# Uno_2022-03-31.net
KiCad netlist of a schematic drawn in Altium Designer
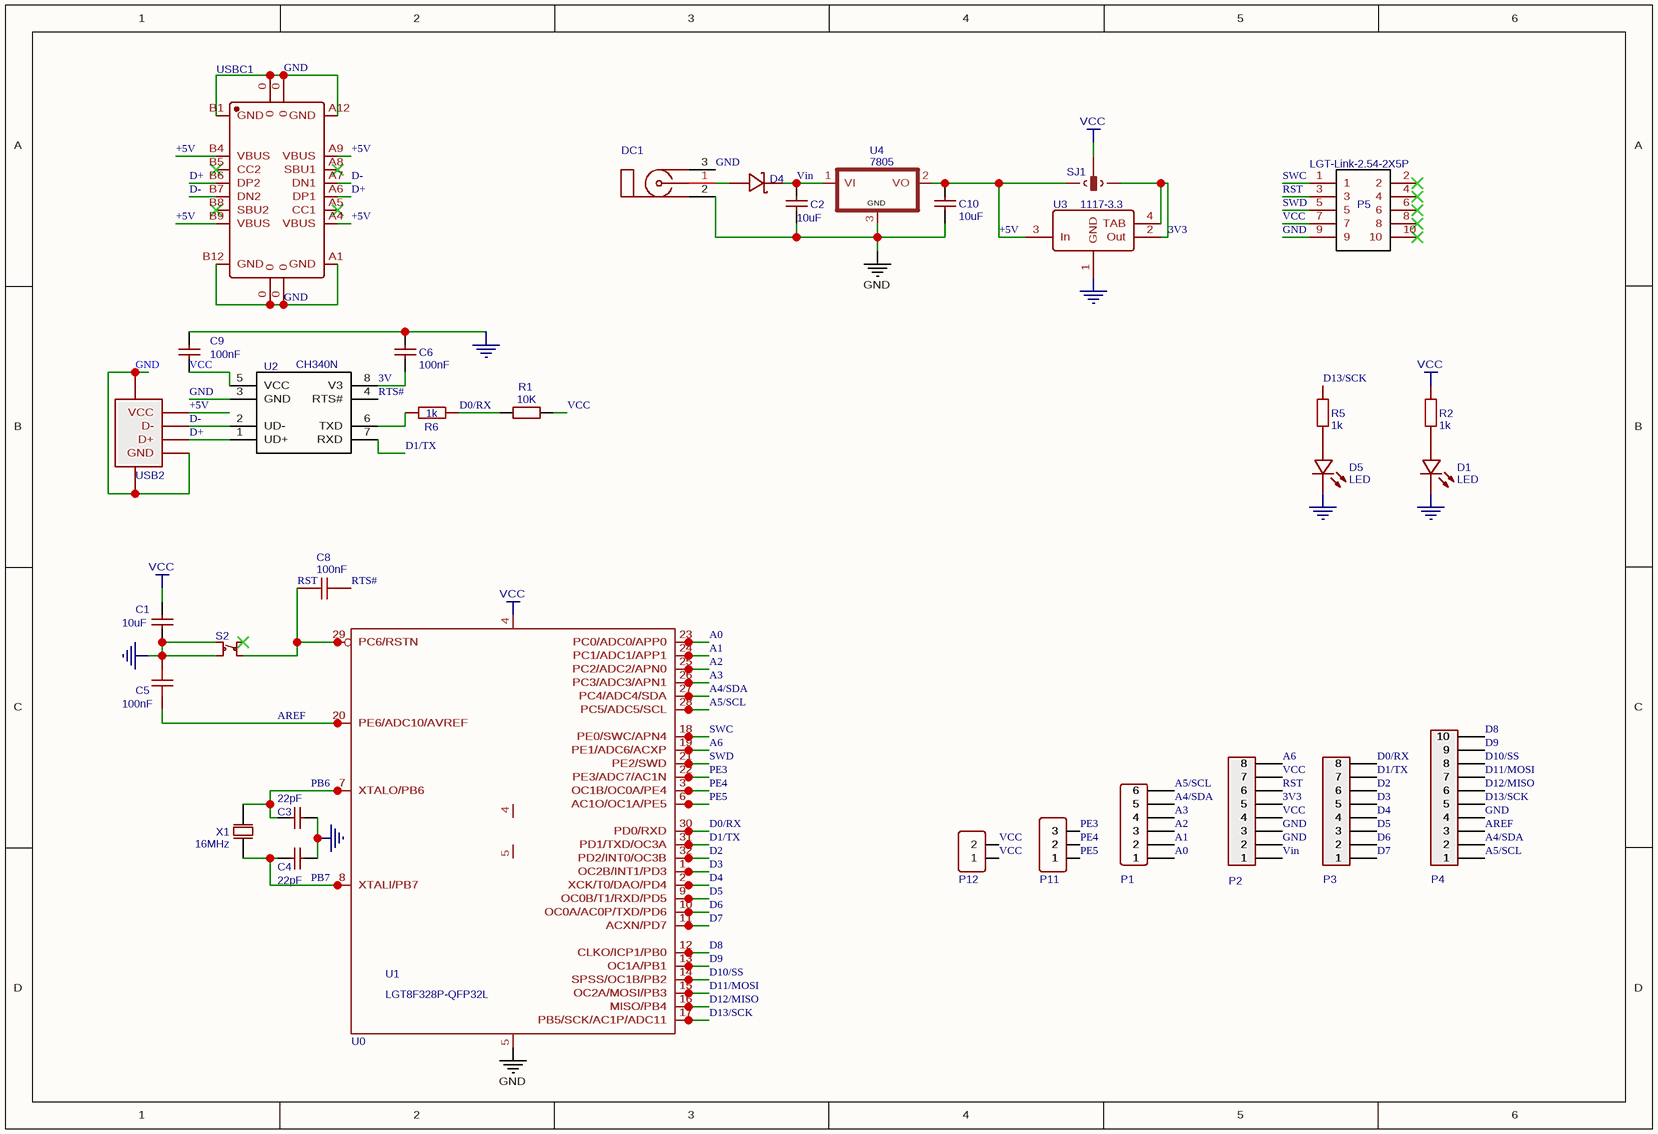
[diagram p0: Uno_2022-03-31.schdoc]

(export (version "E")
  (design (tool "Eeschema 10.0.6"))
  (components
    (comp (ref "C1")
      (value "10uF")
      (fields
        (field (name "VOLTAGE") "25V")
        (field (name "TOLERANCE") "±10%")
        (field (name "BOM_MANUFACTURER PART") "CL21A106KAYNNNE")
      )
      (libsource (lib "altium-import") (part "root_1_10uF_"))
    )
    (comp (ref "C2")
      (value "10uF")
      (fields
        (field (name "VOLTAGE") "25V")
        (field (name "TOLERANCE") "±10%")
        (field (name "BOM_MANUFACTURER PART") "CL21A106KAYNNNE")
      )
      (libsource (lib "altium-import") (part "root_1_10uF_"))
    )
    (comp (ref "C3")
      (value "22pF")
      (fields
        (field (name "VOLTAGE") "50V")
        (field (name "TOLERANCE") "±5%")
        (field (name "BOM_MANUFACTURER PART") "CL10C220JB8NNNC")
      )
      (libsource (lib "altium-import") (part "root_0_22pF_"))
    )
    (comp (ref "C4")
      (value "22pF")
      (fields
        (field (name "VOLTAGE") "50V")
        (field (name "TOLERANCE") "±5%")
        (field (name "BOM_MANUFACTURER PART") "CL10C220JB8NNNC")
      )
      (libsource (lib "altium-import") (part "root_0_22pF_"))
    )
    (comp (ref "C5")
      (value "100nF")
      (fields
        (field (name "VOLTAGE") "50V")
        (field (name "TOLERANCE") "±10%")
        (field (name "BOM_MANUFACTURER PART") "CC0603KRX7R9BB104")
      )
      (libsource (lib "") (part "root_1_100nF__1"))
    )
    (comp (ref "C6")
      (value "100nF")
      (fields
        (field (name "VOLTAGE") "25V")
        (field (name "TOLERANCE") "±10%")
        (field (name "BOM_MANUFACTURER PART") "CL21A106KAYNNNE")
      )
      (libsource (lib "altium-import") (part "root_1_100nF_"))
    )
    (comp (ref "C8")
      (value "100nF")
      (fields
        (field (name "VOLTAGE") "50V")
        (field (name "TOLERANCE") "±10%")
        (field (name "BOM_MANUFACTURER PART") "CC0603KRX7R9BB104")
      )
      (libsource (lib "altium-import") (part "root_2_100nF_"))
    )
    (comp (ref "C9")
      (value "100nF")
      (fields
        (field (name "VOLTAGE") "25V")
        (field (name "TOLERANCE") "±10%")
        (field (name "BOM_MANUFACTURER PART") "CL21A106KAYNNNE")
      )
      (libsource (lib "altium-import") (part "root_1_100nF_"))
    )
    (comp (ref "C10")
      (value "10uF")
      (fields
        (field (name "VOLTAGE") "25V")
        (field (name "TOLERANCE") "±10%")
        (field (name "BOM_MANUFACTURER PART") "CL21A106KAYNNNE")
      )
      (libsource (lib "altium-import") (part "root_1_10uF_"))
    )
    (comp (ref "D1")
      (value "LED")
      (fields (field (name "BOM_MANUFACTURER PART") "?"))
      (libsource (lib "altium-import") (part "root_3_LED_"))
    )
    (comp (ref "D4")
      (value "SS34")
      (fields (field (name "BOM_SUPPLIER PART") "C8678"))
      (libsource (lib "altium-import") (part "root_0_SS34_"))
    )
    (comp (ref "D5")
      (value "LED")
      (fields (field (name "BOM_MANUFACTURER PART") "?"))
      (libsource (lib "altium-import") (part "root_3_LED_"))
    )
    (comp (ref "DC1")
      (value "DC005-2.5MM")
      (fields (field (name "BOM_SUPPLIER PART") "C111573"))
      (libsource (lib "altium-import") (part "root_0_DC005-2.5MM_"))
    )
    (comp (ref "P1")
      (value "Header-Male-2.54_1x6")
      (fields (field (name "BOM_SUPPLIER PART") "C37208"))
      (libsource (lib "altium-import") (part "root_2_Header-Male-2.54_1x6_"))
    )
    (comp (ref "P2")
      (value "Header-Male-2.54_1x8")
      (fields (field (name "BOM_SUPPLIER PART") "E49256"))
      (libsource (lib "altium-import") (part "root_2_Header-Male-2.54_1x8_"))
    )
    (comp (ref "P3")
      (value "Header-Male-2.54_1x8")
      (fields (field (name "BOM_SUPPLIER PART") "E49256"))
      (libsource (lib "altium-import") (part "root_2_Header-Male-2.54_1x8_"))
    )
    (comp (ref "P4")
      (value "Header-Male-2.54_1x10")
      (fields
        (field (name "BOM_MANUFACTURER PART") "Header-Female-1.27_1x10")
        (field (name "BOM_SUPPLIER PART") "C29357")
      )
      (libsource (lib "altium-import") (part "root_2_Header-Male-2.54_1x10_"))
    )
    (comp (ref "P5")
      (value "LGT-Link-2.54-2X5P")
      (fields
        (field (name "BOM_MANUFACTURER PART") "IDC Box 2.54mm 2X5P")
        (field (name "BOM_SUPPLIER PART") "C5665")
      )
      (libsource (lib "altium-import") (part "root_0_LGT-Link-2.54-2X5P_"))
    )
    (comp (ref "P6")
      (value "Header-Female-2.54_1x3")
      (fields (field (name "BOM_SUPPLIER PART") "C146243"))
      (libsource (lib "altium-import") (part "root_2_Header-Female-2.54_1x3_"))
    )
    (comp (ref "P7")
      (value "Header-Male-2.54_1x8")
      (fields (field (name "BOM_SUPPLIER PART") "E49256"))
      (libsource (lib "altium-import") (part "root_2_Header-Male-2.54_1x8_"))
    )
    (comp (ref "P8")
      (value "Header-Male-2.54_1x10")
      (fields
        (field (name "BOM_MANUFACTURER PART") "Header-Female-1.27_1x10")
        (field (name "BOM_SUPPLIER PART") "C29357")
      )
      (libsource (lib "altium-import") (part "root_2_Header-Male-2.54_1x10_"))
    )
    (comp (ref "P9")
      (value "Header-Male-2.54_1x6")
      (fields (field (name "BOM_SUPPLIER PART") "C37208"))
      (libsource (lib "altium-import") (part "root_2_Header-Male-2.54_1x6_"))
    )
    (comp (ref "P10")
      (value "Header-Male-2.54_1x8")
      (fields (field (name "BOM_SUPPLIER PART") "E49256"))
      (libsource (lib "altium-import") (part "root_2_Header-Male-2.54_1x8_"))
    )
    (comp (ref "P11")
      (value "Header-Female-2.54_1x3")
      (fields (field (name "BOM_SUPPLIER PART") "C146243"))
      (libsource (lib "altium-import") (part "root_2_Header-Female-2.54_1x3_"))
    )
    (comp (ref "P12")
      (value "Header-Female-2.54_1x2")
      (fields
        (field (name "BOM_MANUFACTURER PART") "2.54-1*2PFemale")
        (field (name "BOM_SUPPLIER PART") "C49661")
      )
      (libsource (lib "altium-import") (part "root_2_Header-Female-2.54_1x2_"))
    )
    (comp (ref "R1")
      (value "10K")
      (fields
        (field (name "BOM_MANUFACTURER PART") "RS-03K103JT")
        (field (name "BOM_SUPPLIER PART") "C73809")
      )
      (libsource (lib "altium-import") (part "root_0_10K_"))
    )
    (comp (ref "R2")
      (value "1k")
      (fields (field (name "BOM_MANUFACTURER PART") "?"))
      (libsource (lib "altium-import") (part "root_1_1k_"))
    )
    (comp (ref "R5")
      (value "1k")
      (fields (field (name "BOM_MANUFACTURER PART") "?"))
      (libsource (lib "altium-import") (part "root_1_1k_"))
    )
    (comp (ref "R6")
      (value "1k")
      (fields (field (name "BOM_MANUFACTURER PART") "?"))
      (libsource (lib "altium-import") (part "root_0_1k_"))
    )
    (comp (ref "S2")
      (value "TS665CJ-A")
      (fields
        (field (name "BOM_SUPPLIER PART") "C393938")
        (field (name "BOM_MANUFACTURER PART") "TS665CJ")
        (field (name "CONTRIBUTOR") "回收站")
      )
      (libsource (lib "altium-import") (part "root_0_TS665CJ-A_"))
    )
    (comp (ref "SJ1")
      (value "JUMPER-PAD-3-2OF3_NC_BY_PASTE")
      (fields (field (name "BOM_MANUFACTURER PART") "?") (field (name "CONTRIBUTOR") "SparkFun"))
      (libsource (lib "altium-import") (part "root_3_JUMPER-PAD-3-2OF3_NC_BY_PASTE_"))
    )
    (comp (ref "U0")
      (value "LGT8F328P_Socket_LQFP32")
      (fields (field (name "BOM_MANUFACTURER PART") "IC51-0324-1498") (field (name "CONTRIBUTOR") "sino"))
      (libsource (lib "altium-import") (part "root_0_LGT8F328P_Socket_LQFP32_"))
    )
    (comp (ref "U1")
      (value "LGT8F328P-QFP32L")
      (fields (field (name "BOM_MANUFACTURER PART") "?") (field (name "CONTRIBUTOR") "costar"))
      (libsource (lib "altium-import") (part "root_0_LGT8F328P-QFP32L_"))
    )
    (comp (ref "U2")
      (value "CH340N")
      (fields (field (name "BOM_MANUFACTURER PART") "CH330N") (field (name "BOM_SUPPLIER PART") "C108996"))
      (libsource (lib "altium-import") (part "root_0_CH340N_"))
    )
    (comp (ref "U3")
      (value "1117-3.3")
      (fields (field (name "BOM_MANUFACTURER PART") "AMS1117-3.3") (field (name "BOM_SUPPLIER PART") "C6186"))
      (libsource (lib "altium-import") (part "root_0_1117-3.3_"))
    )
    (comp (ref "U4")
      (value "7805")
      (description "Positive VOLTAGE REGULATOR")
      (fields (field (name "BOM_MANUFACTURER PART") "?") (field (name "CONTRIBUTOR") "Adafruit"))
      (libsource (lib "altium-import") (part "root_0_7805_"))
    )
    (comp (ref "USB2")
      (value "USB B 90")
      (fields
        (field (name "BOM_MANUFACTURER PART") "USB BFemale90Degree of iron feet White plastic")
        (field (name "BOM_SUPPLIER PART") "C46392")
      )
      (libsource (lib "altium-import") (part "root_0_USB B 90_"))
    )
    (comp (ref "USBC1")
      (value "TYPE-C-31-M-12")
      (fields (field (name "BOM_SUPPLIER PART") "C165948") (field (name "CONTRIBUTOR") "LCSC"))
      (libsource (lib "altium-import") (part "root_0_TYPE-C-31-M-12_"))
    )
    (comp (ref "X1")
      (value "16MHz")
      (fields
        (field (name "BOM_SUPPLIER PART") "C188202")
        (field (name "BOM_MANUFACTURER PART") "X49SD16MSB2SI")
        (field (name "CONTRIBUTOR") "LCSC")
      )
      (libsource (lib "altium-import") (part "root_1_16MHz_"))
    )
  )
  (nets
    (net (code "1") (name "/+5V") (class "Default")
      (node (ref "C10") (pin "2") (pinfunction "2_2") (pintype "passive"))
      (node (ref "SJ1") (pin "3") (pinfunction "3_3") (pintype "passive"))
      (node (ref "U3") (pin "3") (pinfunction "In_3") (pintype "passive"))
      (node (ref "U4") (pin "2") (pinfunction "VO_2") (pintype "passive"))
      (node (ref "USB2") (pin "1") (pinfunction "VCC_1") (pintype "passive"))
      (node (ref "USBC1") (pin "A4") (pinfunction "VBUS_A4") (pintype "passive"))
      (node (ref "USBC1") (pin "A9") (pinfunction "VBUS_A9") (pintype "passive"))
      (node (ref "USBC1") (pin "B4") (pinfunction "VBUS_B4") (pintype "passive"))
      (node (ref "USBC1") (pin "B9") (pinfunction "VBUS_B9") (pintype "passive"))
    )
    (net (code "2") (name "/3V") (class "Default")
      (node (ref "C6") (pin "1") (pinfunction "1_1") (pintype "passive"))
      (node (ref "U2") (pin "8") (pinfunction "V3_8") (pintype "passive"))
    )
    (net (code "3") (name "/3V3") (class "Default")
      (node (ref "P10") (pin "5") (pinfunction "5_5") (pintype "passive"))
      (node (ref "P2") (pin "5") (pinfunction "5_5") (pintype "passive"))
      (node (ref "SJ1") (pin "1") (pinfunction "1_1") (pintype "passive"))
      (node (ref "U3") (pin "2") (pinfunction "Out_2") (pintype "passive"))
      (node (ref "U3") (pin "4") (pinfunction "TAB_4") (pintype "passive"))
    )
    (net (code "4") (name "/A0") (class "Default")
      (node (ref "P1") (pin "1") (pinfunction "1_1") (pintype "passive"))
      (node (ref "P9") (pin "1") (pinfunction "1_1") (pintype "passive"))
      (node (ref "U0") (pin "23") (pinfunction "PC0/ADC0/APP0_23") (pintype "passive"))
      (node (ref "U1") (pin "23") (pinfunction "PC0/ADC0/APP0_23") (pintype "passive"))
    )
    (net (code "5") (name "/A1") (class "Default")
      (node (ref "P1") (pin "2") (pinfunction "2_2") (pintype "passive"))
      (node (ref "P9") (pin "2") (pinfunction "2_2") (pintype "passive"))
      (node (ref "U0") (pin "24") (pinfunction "PC1/ADC1/APP1_24") (pintype "passive"))
      (node (ref "U1") (pin "24") (pinfunction "PC1/ADC1/APP1_24") (pintype "passive"))
    )
    (net (code "6") (name "/A2") (class "Default")
      (node (ref "P1") (pin "3") (pinfunction "3_3") (pintype "passive"))
      (node (ref "P9") (pin "3") (pinfunction "3_3") (pintype "passive"))
      (node (ref "U0") (pin "25") (pinfunction "PC2/ADC2/APN0_25") (pintype "passive"))
      (node (ref "U1") (pin "25") (pinfunction "PC2/ADC2/APN0_25") (pintype "passive"))
    )
    (net (code "7") (name "/A3") (class "Default")
      (node (ref "P1") (pin "4") (pinfunction "4_4") (pintype "passive"))
      (node (ref "P9") (pin "4") (pinfunction "4_4") (pintype "passive"))
      (node (ref "U0") (pin "26") (pinfunction "PC3/ADC3/APN1_26") (pintype "passive"))
      (node (ref "U1") (pin "26") (pinfunction "PC3/ADC3/APN1_26") (pintype "passive"))
    )
    (net (code "8") (name "/A4{slash}SDA") (class "Default")
      (node (ref "P1") (pin "5") (pinfunction "5_5") (pintype "passive"))
      (node (ref "P4") (pin "2") (pinfunction "2_2") (pintype "passive"))
      (node (ref "P8") (pin "2") (pinfunction "2_2") (pintype "passive"))
      (node (ref "P9") (pin "5") (pinfunction "5_5") (pintype "passive"))
      (node (ref "U0") (pin "27") (pinfunction "PC4/ADC4/SDA_27") (pintype "passive"))
      (node (ref "U1") (pin "27") (pinfunction "PC4/ADC4/SDA_27") (pintype "passive"))
    )
    (net (code "9") (name "/A5{slash}SCL") (class "Default")
      (node (ref "P1") (pin "6") (pinfunction "6_6") (pintype "passive"))
      (node (ref "P4") (pin "1") (pinfunction "1_1") (pintype "passive"))
      (node (ref "P8") (pin "1") (pinfunction "1_1") (pintype "passive"))
      (node (ref "P9") (pin "6") (pinfunction "6_6") (pintype "passive"))
      (node (ref "U0") (pin "28") (pinfunction "PC5/ADC5/SCL_28") (pintype "passive"))
      (node (ref "U1") (pin "28") (pinfunction "PC5/ADC5/SCL_28") (pintype "passive"))
    )
    (net (code "10") (name "/A6") (class "Default")
      (node (ref "P10") (pin "8") (pinfunction "8_8") (pintype "passive"))
      (node (ref "P2") (pin "8") (pinfunction "8_8") (pintype "passive"))
      (node (ref "U0") (pin "19") (pinfunction "PE1/ADC6/ACXP_19") (pintype "passive"))
      (node (ref "U1") (pin "19") (pinfunction "PE1/ADC6/ACXP_19") (pintype "passive"))
    )
    (net (code "11") (name "/AREF") (class "Default")
      (node (ref "C5") (pin "1") (pinfunction "1_1") (pintype "passive"))
      (node (ref "P4") (pin "3") (pinfunction "3_3") (pintype "passive"))
      (node (ref "P8") (pin "3") (pinfunction "3_3") (pintype "passive"))
      (node (ref "U0") (pin "20") (pinfunction "PE6/ADC10/AVREF_20") (pintype "passive"))
      (node (ref "U1") (pin "20") (pinfunction "PE6/ADC10/AVREF_20") (pintype "passive"))
    )
    (net (code "12") (name "/D+") (class "Default")
      (node (ref "U2") (pin "1") (pinfunction "UD+_1") (pintype "passive"))
      (node (ref "USB2") (pin "3") (pinfunction "D+_3") (pintype "passive"))
      (node (ref "USBC1") (pin "A6") (pinfunction "DP1_A6") (pintype "passive"))
      (node (ref "USBC1") (pin "B6") (pinfunction "DP2_B6") (pintype "passive"))
    )
    (net (code "13") (name "/D-") (class "Default")
      (node (ref "U2") (pin "2") (pinfunction "UD-_2") (pintype "passive"))
      (node (ref "USB2") (pin "2") (pinfunction "D-_2") (pintype "passive"))
      (node (ref "USBC1") (pin "A7") (pinfunction "DN1_A7") (pintype "passive"))
      (node (ref "USBC1") (pin "B7") (pinfunction "DN2_B7") (pintype "passive"))
    )
    (net (code "14") (name "/D0{slash}RX") (class "Default")
      (node (ref "P3") (pin "8") (pinfunction "8_8") (pintype "passive"))
      (node (ref "P7") (pin "8") (pinfunction "8_8") (pintype "passive"))
      (node (ref "R1") (pin "1") (pinfunction "1_1") (pintype "passive"))
      (node (ref "R6") (pin "2") (pinfunction "2_2") (pintype "passive"))
      (node (ref "U0") (pin "30") (pinfunction "PD0/RXD_30") (pintype "passive"))
      (node (ref "U1") (pin "30") (pinfunction "PD0/RXD_30") (pintype "passive"))
    )
    (net (code "15") (name "/D1{slash}TX") (class "Default")
      (node (ref "P3") (pin "7") (pinfunction "7_7") (pintype "passive"))
      (node (ref "P7") (pin "7") (pinfunction "7_7") (pintype "passive"))
      (node (ref "U0") (pin "31") (pinfunction "PD1/TXD/OC3A_31") (pintype "passive"))
      (node (ref "U1") (pin "31") (pinfunction "PD1/TXD/OC3A_31") (pintype "passive"))
      (node (ref "U2") (pin "7") (pinfunction "RXD_7") (pintype "passive"))
    )
    (net (code "16") (name "/D2") (class "Default")
      (node (ref "P3") (pin "6") (pinfunction "6_6") (pintype "passive"))
      (node (ref "P7") (pin "6") (pinfunction "6_6") (pintype "passive"))
      (node (ref "U0") (pin "32") (pinfunction "PD2/INT0/OC3B_32") (pintype "passive"))
      (node (ref "U1") (pin "32") (pinfunction "PD2/INT0/OC3B_32") (pintype "passive"))
    )
    (net (code "17") (name "/D3") (class "Default")
      (node (ref "P3") (pin "5") (pinfunction "5_5") (pintype "passive"))
      (node (ref "P7") (pin "5") (pinfunction "5_5") (pintype "passive"))
      (node (ref "U0") (pin "1") (pinfunction "OC2B/INT1/PD3_1") (pintype "passive"))
      (node (ref "U1") (pin "1") (pinfunction "OC2B/INT1/PD3_1") (pintype "passive"))
    )
    (net (code "18") (name "/D4") (class "Default")
      (node (ref "P3") (pin "4") (pinfunction "4_4") (pintype "passive"))
      (node (ref "P7") (pin "4") (pinfunction "4_4") (pintype "passive"))
      (node (ref "U0") (pin "2") (pinfunction "XCK/T0/DAO/PD4_2") (pintype "passive"))
      (node (ref "U1") (pin "2") (pinfunction "XCK/T0/DAO/PD4_2") (pintype "passive"))
    )
    (net (code "19") (name "/D5") (class "Default")
      (node (ref "P3") (pin "3") (pinfunction "3_3") (pintype "passive"))
      (node (ref "P7") (pin "3") (pinfunction "3_3") (pintype "passive"))
      (node (ref "U0") (pin "9") (pinfunction "OC0B/T1/RXD/PD5_9") (pintype "passive"))
      (node (ref "U1") (pin "9") (pinfunction "OC0B/T1/RXD/PD5_9") (pintype "passive"))
    )
    (net (code "20") (name "/D6") (class "Default")
      (node (ref "P3") (pin "2") (pinfunction "2_2") (pintype "passive"))
      (node (ref "P7") (pin "2") (pinfunction "2_2") (pintype "passive"))
      (node (ref "U0") (pin "10") (pinfunction "OC0A/AC0P/TXD/PD6_10") (pintype "passive"))
      (node (ref "U1") (pin "10") (pinfunction "OC0A/AC0P/TXD/PD6_10") (pintype "passive"))
    )
    (net (code "21") (name "/D7") (class "Default")
      (node (ref "P3") (pin "1") (pinfunction "1_1") (pintype "passive"))
      (node (ref "P7") (pin "1") (pinfunction "1_1") (pintype "passive"))
      (node (ref "U0") (pin "11") (pinfunction "ACXN/PD7_11") (pintype "passive"))
      (node (ref "U1") (pin "11") (pinfunction "ACXN/PD7_11") (pintype "passive"))
    )
    (net (code "22") (name "/D8") (class "Default")
      (node (ref "P4") (pin "10") (pinfunction "10_10") (pintype "passive"))
      (node (ref "P8") (pin "10") (pinfunction "10_10") (pintype "passive"))
      (node (ref "U0") (pin "12") (pinfunction "CLKO/ICP1/PB0_12") (pintype "passive"))
      (node (ref "U1") (pin "12") (pinfunction "CLKO/ICP1/PB0_12") (pintype "passive"))
    )
    (net (code "23") (name "/D9") (class "Default")
      (node (ref "P4") (pin "9") (pinfunction "9_9") (pintype "passive"))
      (node (ref "P8") (pin "9") (pinfunction "9_9") (pintype "passive"))
      (node (ref "U0") (pin "13") (pinfunction "OC1A/PB1_13") (pintype "passive"))
      (node (ref "U1") (pin "13") (pinfunction "OC1A/PB1_13") (pintype "passive"))
    )
    (net (code "24") (name "/D10{slash}SS") (class "Default")
      (node (ref "P4") (pin "8") (pinfunction "8_8") (pintype "passive"))
      (node (ref "P8") (pin "8") (pinfunction "8_8") (pintype "passive"))
      (node (ref "U0") (pin "14") (pinfunction "SPSS/OC1B/PB2_14") (pintype "passive"))
      (node (ref "U1") (pin "14") (pinfunction "SPSS/OC1B/PB2_14") (pintype "passive"))
    )
    (net (code "25") (name "/D11{slash}MOSI") (class "Default")
      (node (ref "P4") (pin "7") (pinfunction "7_7") (pintype "passive"))
      (node (ref "P8") (pin "7") (pinfunction "7_7") (pintype "passive"))
      (node (ref "U0") (pin "15") (pinfunction "OC2A/MOSI/PB3_15") (pintype "passive"))
      (node (ref "U1") (pin "15") (pinfunction "OC2A/MOSI/PB3_15") (pintype "passive"))
    )
    (net (code "26") (name "/D12{slash}MISO") (class "Default")
      (node (ref "P4") (pin "6") (pinfunction "6_6") (pintype "passive"))
      (node (ref "P8") (pin "6") (pinfunction "6_6") (pintype "passive"))
      (node (ref "U0") (pin "16") (pinfunction "MISO/PB4_16") (pintype "passive"))
      (node (ref "U1") (pin "16") (pinfunction "MISO/PB4_16") (pintype "passive"))
    )
    (net (code "27") (name "/D13{slash}SCK") (class "Default")
      (node (ref "P4") (pin "5") (pinfunction "5_5") (pintype "passive"))
      (node (ref "P8") (pin "5") (pinfunction "5_5") (pintype "passive"))
      (node (ref "R5") (pin "2") (pinfunction "2_2") (pintype "passive"))
      (node (ref "U0") (pin "17") (pinfunction "PB5/SCK/AC1P/ADC11_17") (pintype "passive"))
      (node (ref "U1") (pin "17") (pinfunction "PB5/SCK/AC1P/ADC11_17") (pintype "passive"))
    )
    (net (code "28") (name "/PB6") (class "Default")
      (node (ref "C3") (pin "1") (pinfunction "1_1") (pintype "passive"))
      (node (ref "U0") (pin "7") (pinfunction "XTALO/PB6_7") (pintype "passive"))
      (node (ref "U1") (pin "7") (pinfunction "XTALO/PB6_7") (pintype "passive"))
      (node (ref "X1") (pin "2") (pinfunction "OSC2_2") (pintype "passive"))
    )
    (net (code "29") (name "/PB7") (class "Default")
      (node (ref "C4") (pin "1") (pinfunction "1_1") (pintype "passive"))
      (node (ref "U0") (pin "8") (pinfunction "XTALI/PB7_8") (pintype "passive"))
      (node (ref "U1") (pin "8") (pinfunction "XTALI/PB7_8") (pintype "passive"))
      (node (ref "X1") (pin "1") (pinfunction "OSC1_1") (pintype "passive"))
    )
    (net (code "30") (name "/PE3") (class "Default")
      (node (ref "P11") (pin "3") (pinfunction "3_3") (pintype "passive"))
      (node (ref "P6") (pin "3") (pinfunction "3_3") (pintype "passive"))
      (node (ref "U0") (pin "22") (pinfunction "PE3/ADC7/AC1N_22") (pintype "passive"))
      (node (ref "U1") (pin "22") (pinfunction "PE3/ADC7/AC1N_22") (pintype "passive"))
    )
    (net (code "31") (name "/PE4") (class "Default")
      (node (ref "P11") (pin "2") (pinfunction "2_2") (pintype "passive"))
      (node (ref "P6") (pin "2") (pinfunction "2_2") (pintype "passive"))
      (node (ref "U0") (pin "3") (pinfunction "OC1B/OC0A/PE4_3") (pintype "passive"))
      (node (ref "U1") (pin "3") (pinfunction "OC1B/OC0A/PE4_3") (pintype "passive"))
    )
    (net (code "32") (name "/PE5") (class "Default")
      (node (ref "P11") (pin "1") (pinfunction "1_1") (pintype "passive"))
      (node (ref "P6") (pin "1") (pinfunction "1_1") (pintype "passive"))
      (node (ref "U0") (pin "6") (pinfunction "AC1O/OC1A/PE5_6") (pintype "passive"))
      (node (ref "U1") (pin "6") (pinfunction "AC1O/OC1A/PE5_6") (pintype "passive"))
    )
    (net (code "33") (name "/RST") (class "Default")
      (node (ref "C8") (pin "2") (pinfunction "2_2") (pintype "passive"))
      (node (ref "P10") (pin "6") (pinfunction "6_6") (pintype "passive"))
      (node (ref "P2") (pin "6") (pinfunction "6_6") (pintype "passive"))
      (node (ref "P5") (pin "3") (pinfunction "3_3") (pintype "passive"))
      (node (ref "S2") (pin "4") (pinfunction "D_4") (pintype "passive"))
      (node (ref "U0") (pin "29") (pinfunction "PC6/RSTN_29") (pintype "passive"))
      (node (ref "U1") (pin "29") (pinfunction "PC6/RSTN_29") (pintype "passive"))
    )
    (net (code "34") (name "/RTS#") (class "Default")
      (node (ref "C8") (pin "1") (pinfunction "1_1") (pintype "passive"))
      (node (ref "U2") (pin "4") (pinfunction "RTS#_4") (pintype "passive"))
    )
    (net (code "35") (name "/SWC") (class "Default")
      (node (ref "P5") (pin "1") (pinfunction "1_1") (pintype "passive"))
      (node (ref "U0") (pin "18") (pinfunction "PE0/SWC/APN4_18") (pintype "passive"))
      (node (ref "U1") (pin "18") (pinfunction "PE0/SWC/APN4_18") (pintype "passive"))
    )
    (net (code "36") (name "/SWD") (class "Default")
      (node (ref "P5") (pin "5") (pinfunction "5_5") (pintype "passive"))
      (node (ref "U0") (pin "21") (pinfunction "PE2/SWD_21") (pintype "passive"))
      (node (ref "U1") (pin "21") (pinfunction "PE2/SWD_21") (pintype "passive"))
    )
    (net (code "37") (name "/Vin") (class "Default")
      (node (ref "C2") (pin "2") (pinfunction "2_2") (pintype "passive"))
      (node (ref "D4") (pin "2") (pinfunction "K_2") (pintype "passive"))
      (node (ref "P10") (pin "1") (pinfunction "1_1") (pintype "passive"))
      (node (ref "P2") (pin "1") (pinfunction "1_1") (pintype "passive"))
      (node (ref "U4") (pin "1") (pinfunction "VI_1") (pintype "passive"))
    )
    (net (code "38") (name "GND") (class "Default")
      (node (ref "C1") (pin "1") (pinfunction "1_1") (pintype "passive"))
      (node (ref "C10") (pin "1") (pinfunction "1_1") (pintype "passive"))
      (node (ref "C2") (pin "1") (pinfunction "1_1") (pintype "passive"))
      (node (ref "C3") (pin "2") (pinfunction "2_2") (pintype "passive"))
      (node (ref "C4") (pin "2") (pinfunction "2_2") (pintype "passive"))
      (node (ref "C5") (pin "2") (pinfunction "2_2") (pintype "passive"))
      (node (ref "C6") (pin "2") (pinfunction "2_2") (pintype "passive"))
      (node (ref "C9") (pin "2") (pinfunction "2_2") (pintype "passive"))
      (node (ref "D1") (pin "2") (pinfunction "K_2") (pintype "passive"))
      (node (ref "D5") (pin "2") (pinfunction "K_2") (pintype "passive"))
      (node (ref "DC1") (pin "2") (pinfunction "2_2") (pintype "passive"))
      (node (ref "DC1") (pin "3") (pinfunction "3_3") (pintype "passive"))
      (node (ref "P10") (pin "2") (pinfunction "2_2") (pintype "passive"))
      (node (ref "P10") (pin "3") (pinfunction "3_3") (pintype "passive"))
      (node (ref "P2") (pin "2") (pinfunction "2_2") (pintype "passive"))
      (node (ref "P2") (pin "3") (pinfunction "3_3") (pintype "passive"))
      (node (ref "P4") (pin "4") (pinfunction "4_4") (pintype "passive"))
      (node (ref "P5") (pin "9") (pinfunction "9_9") (pintype "passive"))
      (node (ref "P8") (pin "4") (pinfunction "4_4") (pintype "passive"))
      (node (ref "S2") (pin "1") (pinfunction "A_1") (pintype "passive"))
      (node (ref "S2") (pin "2") (pinfunction "B_2") (pintype "passive"))
      (node (ref "U0") (pin "5") (pinfunction "GND_5") (pintype "passive"))
      (node (ref "U2") (pin "3") (pinfunction "GND_3") (pintype "passive"))
      (node (ref "U3") (pin "1") (pinfunction "GND_1") (pintype "passive"))
      (node (ref "U4") (pin "3") (pinfunction "GND_3") (pintype "passive"))
      (node (ref "USB2") (pin "4") (pinfunction "GND_4") (pintype "passive"))
      (node (ref "USB2") (pin "5") (pinfunction "5_5") (pintype "passive"))
      (node (ref "USB2") (pin "6") (pinfunction "6_6") (pintype "passive"))
      (node (ref "USBC1") (pin "0") (pinfunction "0_0") (pintype "passive"))
      (node (ref "USBC1") (pin "A1") (pinfunction "GND_A1") (pintype "passive"))
      (node (ref "USBC1") (pin "A12") (pinfunction "GND_A12") (pintype "passive"))
      (node (ref "USBC1") (pin "B1") (pinfunction "GND_B1") (pintype "passive"))
      (node (ref "USBC1") (pin "B12") (pinfunction "GND_B12") (pintype "passive"))
    )
    (net (code "39") (name "Net-(D1-A)") (class "Default")
      (node (ref "D1") (pin "1") (pinfunction "A_1") (pintype "passive"))
      (node (ref "R2") (pin "1") (pinfunction "1_1") (pintype "passive"))
    )
    (net (code "40") (name "Net-(D4-A)") (class "Default")
      (node (ref "D4") (pin "1") (pinfunction "A_1") (pintype "passive"))
      (node (ref "DC1") (pin "1") (pinfunction "VCC_1") (pintype "passive"))
    )
    (net (code "41") (name "Net-(D5-A)") (class "Default")
      (node (ref "D5") (pin "1") (pinfunction "A_1") (pintype "passive"))
      (node (ref "R5") (pin "1") (pinfunction "1_1") (pintype "passive"))
    )
    (net (code "42") (name "Net-(U2-TXD)") (class "Default")
      (node (ref "R6") (pin "1") (pinfunction "1_1") (pintype "passive"))
      (node (ref "U2") (pin "6") (pinfunction "TXD_6") (pintype "passive"))
    )
    (net (code "43") (name "VCC") (class "Default")
      (node (ref "C1") (pin "2") (pinfunction "2_2") (pintype "passive"))
      (node (ref "C9") (pin "1") (pinfunction "1_1") (pintype "passive"))
      (node (ref "P10") (pin "4") (pinfunction "4_4") (pintype "passive"))
      (node (ref "P10") (pin "7") (pinfunction "7_7") (pintype "passive"))
      (node (ref "P12") (pin "1") (pinfunction "1_1") (pintype "passive"))
      (node (ref "P12") (pin "2") (pinfunction "2_2") (pintype "passive"))
      (node (ref "P2") (pin "4") (pinfunction "4_4") (pintype "passive"))
      (node (ref "P2") (pin "7") (pinfunction "7_7") (pintype "passive"))
      (node (ref "P5") (pin "7") (pinfunction "7_7") (pintype "passive"))
      (node (ref "R1") (pin "2") (pinfunction "2_2") (pintype "passive"))
      (node (ref "R2") (pin "2") (pinfunction "2_2") (pintype "passive"))
      (node (ref "SJ1") (pin "2") (pinfunction "2_2") (pintype "passive"))
      (node (ref "U0") (pin "4") (pinfunction "VCC_4") (pintype "passive"))
      (node (ref "U2") (pin "5") (pinfunction "VCC_5") (pintype "passive"))
    )
    (net (code "44") (name "unconnected-(P5-Pad2)") (class "Default")
      (node (ref "P5") (pin "2") (pinfunction "2_2") (pintype "passive+no_connect"))
    )
    (net (code "45") (name "unconnected-(P5-Pad4)") (class "Default")
      (node (ref "P5") (pin "4") (pinfunction "4_4") (pintype "passive+no_connect"))
    )
    (net (code "46") (name "unconnected-(P5-Pad6)") (class "Default")
      (node (ref "P5") (pin "6") (pinfunction "6_6") (pintype "passive+no_connect"))
    )
    (net (code "47") (name "unconnected-(P5-Pad8)") (class "Default")
      (node (ref "P5") (pin "8") (pinfunction "8_8") (pintype "passive+no_connect"))
    )
    (net (code "48") (name "unconnected-(P5-Pad10)") (class "Default")
      (node (ref "P5") (pin "10") (pinfunction "10_10") (pintype "passive+no_connect"))
    )
    (net (code "49") (name "unconnected-(S2-C-Pad3)") (class "Default")
      (node (ref "S2") (pin "3") (pinfunction "C_3") (pintype "passive+no_connect"))
    )
    (net (code "50") (name "unconnected-(U1-GND-Pad5)") (class "Default")
      (node (ref "U1") (pin "5") (pinfunction "GND_5") (pintype "passive"))
    )
    (net (code "51") (name "unconnected-(U1-VCC-Pad4)") (class "Default")
      (node (ref "U1") (pin "4") (pinfunction "VCC_4") (pintype "passive"))
    )
    (net (code "52") (name "unconnected-(USBC1-CC1-PadA5)") (class "Default")
      (node (ref "USBC1") (pin "A5") (pinfunction "CC1_A5") (pintype "passive+no_connect"))
    )
    (net (code "53") (name "unconnected-(USBC1-CC2-PadB5)") (class "Default")
      (node (ref "USBC1") (pin "B5") (pinfunction "CC2_B5") (pintype "passive+no_connect"))
    )
    (net (code "54") (name "unconnected-(USBC1-SBU1-PadA8)") (class "Default")
      (node (ref "USBC1") (pin "A8") (pinfunction "SBU1_A8") (pintype "passive+no_connect"))
    )
    (net (code "55") (name "unconnected-(USBC1-SBU2-PadB8)") (class "Default")
      (node (ref "USBC1") (pin "B8") (pinfunction "SBU2_B8") (pintype "passive+no_connect"))
    )
  )
)
